# Aux_MCU_ATmega16U4.net
KiCad netlist of a schematic drawn in Altium Designer
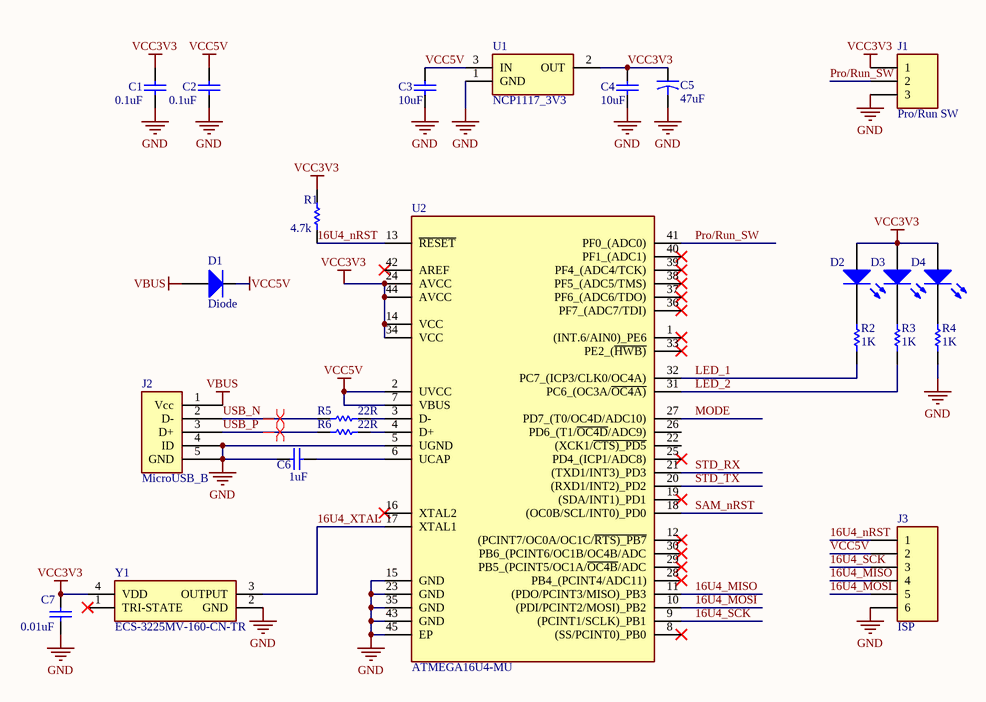
[diagram p0: Aux_MCU_ATmega16U4.SchDoc]

(export (version "E")
  (design (tool "Eeschema 10.0.6"))
  (components
    (comp (ref "C1")
      (value "0.1uF")
      (footprint "SMD0603")
      (description "Capacitor (Semiconductor SIM Model)")
      (fields (field (name "PUBLISHER") "Altium Limited"))
      (libsource (lib "Miscellaneous Devices") (part "Cap Semi"))
    )
    (comp (ref "C2")
      (value "0.1uF")
      (footprint "SMD0603")
      (description "Capacitor (Semiconductor SIM Model)")
      (fields (field (name "PUBLISHER") "Altium Limited"))
      (libsource (lib "Miscellaneous Devices") (part "Cap Semi"))
    )
    (comp (ref "C3")
      (value "10uF")
      (footprint "SMD0603")
      (description "Capacitor (Semiconductor SIM Model)")
      (fields (field (name "PUBLISHER") "Altium Limited"))
      (libsource (lib "Miscellaneous Devices") (part "Cap Semi"))
    )
    (comp (ref "C4")
      (value "10uF")
      (footprint "SMD0603")
      (description "Capacitor (Semiconductor SIM Model)")
      (fields (field (name "PUBLISHER") "Altium Limited"))
      (libsource (lib "Miscellaneous Devices") (part "Cap Semi"))
    )
    (comp (ref "C5")
      (value "47uF")
      (footprint "TAJ_CLASS_C")
      (description "Capacitor")
      (fields (field (name "PUBLISHER") "Altium Limited"))
      (libsource (lib "SRV8") (part "Cap2"))
    )
    (comp (ref "C6")
      (value "1uF")
      (footprint "SMD0603")
      (description "Capacitor (Semiconductor SIM Model)")
      (fields (field (name "PUBLISHER") "Altium Limited"))
      (libsource (lib "Miscellaneous Devices") (part "Cap Semi"))
    )
    (comp (ref "C7")
      (value "0.01uF")
      (footprint "SMD0603")
      (description "Capacitor (Semiconductor SIM Model)")
      (fields (field (name "PUBLISHER") "Altium Limited"))
      (libsource (lib "Miscellaneous Devices") (part "Cap Semi"))
    )
    (comp (ref "D1")
      (value "Diode")
      (footprint "SMB_DIODE_B130LB")
      (description "Default Diode")
      (fields (field (name "PUBLISHER") "Altium Limited"))
      (libsource (lib "Miscellaneous Devices") (part "Diode"))
    )
    (comp (ref "D2")
      (value "LED0")
      (footprint "SMD0603_LED")
      (description "Typical INFRARED GaAs LED")
      (fields (field (name "PUBLISHER") "Altium Limited"))
      (libsource (lib "Miscellaneous Devices") (part "LED0"))
    )
    (comp (ref "D3")
      (value "LED0")
      (footprint "SMD0603_LED")
      (description "Typical INFRARED GaAs LED")
      (fields (field (name "PUBLISHER") "Altium Limited"))
      (libsource (lib "Miscellaneous Devices") (part "LED0"))
    )
    (comp (ref "D4")
      (value "LED0")
      (footprint "SMD0603_LED")
      (description "Typical INFRARED GaAs LED")
      (fields (field (name "PUBLISHER") "Altium Limited"))
      (libsource (lib "Miscellaneous Devices") (part "LED0"))
    )
    (comp (ref "J1")
      (value "Pro/Run SW")
      (footprint "SLIDE_SW_3P")
      (description "Program/Run Switch")
      (libsource (lib "ATSAME54p20a_Ethernet") (part "Pro/Run SW"))
    )
    (comp (ref "J2")
      (value "MicroUSB_B")
      (footprint "micro_usb_molex_105017-0001")
      (libsource (lib "ATSAME54p20a_Ethernet") (part "MicroUSB_B"))
    )
    (comp (ref "J3") (value "ISP") (footprint "ISP") (libsource (lib "ATSAME54p20a_Ethernet") (part "ISP")))
    (comp (ref "R1")
      (value "4.7k")
      (footprint "SMD0603")
      (description "Semiconductor Resistor")
      (fields (field (name "Comment") "4.7K"))
      (libsource (lib "*") (part "Res"))
    )
    (comp (ref "R2")
      (value "1K")
      (footprint "SMD0603")
      (description "Semiconductor Resistor")
      (fields (field (name "PUBLISHER") "Altium Limited"))
      (libsource (lib "Miscellaneous Devices") (part "Res Semi"))
    )
    (comp (ref "R3")
      (value "1K")
      (footprint "SMD0603")
      (description "Semiconductor Resistor")
      (fields (field (name "PUBLISHER") "Altium Limited"))
      (libsource (lib "Miscellaneous Devices") (part "Res Semi"))
    )
    (comp (ref "R4")
      (value "1K")
      (footprint "SMD0603")
      (description "Semiconductor Resistor")
      (fields (field (name "PUBLISHER") "Altium Limited"))
      (libsource (lib "Miscellaneous Devices") (part "Res Semi"))
    )
    (comp (ref "R5")
      (value "22R")
      (footprint "SMD0603")
      (description "Semiconductor Resistor")
      (libsource (lib "*") (part "Res"))
    )
    (comp (ref "R6")
      (value "22R")
      (footprint "SMD0603")
      (description "Semiconductor Resistor")
      (libsource (lib "*") (part "Res"))
    )
    (comp (ref "U1")
      (value "NCP1117_3V3")
      (footprint "SOT-223-2")
      (description "IC REG 3.3V 1A DPAC")
      (libsource (lib "ATSAME54p20a_Ethernet") (part "NCP1117_3V3"))
    )
    (comp (ref "U2")
      (value "ATMEGA16U4-MU")
      (footprint "ATSAME54p20a_Ethernet:QFN50P700X700X100-45N-D")
      (description "Integrated Circuit")
      (libsource (lib "ATSAME54p20a_Ethernet") (part "ATMEGA16U4-MU"))
    )
    (comp (ref "Y1")
      (value "ECS-3225MV-160-CN-TR")
      (footprint "OSC3225")
      (description "Crystal or Oscillator")
      (fields (field (name "MOUSER2 PART NUMBER") "520-3225MV-160-CNT"))
      (libsource (lib "ATSAME54p20a_Ethernet") (part "ECS-3225MV-160-CN-TR"))
    )
  )
  (nets
    (net (code "1") (name "/16U4_MISO") (class "Default")
      (node (ref "J3") (pin "4") (pinfunction "4_4") (pintype "passive"))
      (node (ref "U2") (pin "11") (pinfunction "(PDO/PCINT3/MISO)_PB3_11") (pintype "passive"))
    )
    (net (code "2") (name "/16U4_MOSI") (class "Default")
      (node (ref "J3") (pin "5") (pinfunction "5_5") (pintype "passive"))
      (node (ref "U2") (pin "10") (pinfunction "(PDI/PCINT2/MOSI)_PB2_10") (pintype "passive"))
    )
    (net (code "3") (name "/16U4_SCK") (class "Default")
      (node (ref "J3") (pin "3") (pinfunction "3_3") (pintype "passive"))
      (node (ref "U2") (pin "9") (pinfunction "(PCINT1/SCLK)_PB1_9") (pintype "passive"))
    )
    (net (code "4") (name "/16U4_XTAL") (class "Default")
      (node (ref "U2") (pin "17") (pinfunction "XTAL1_17") (pintype "passive"))
      (node (ref "Y1") (pin "3") (pinfunction "OUTPUT_3") (pintype "passive"))
    )
    (net (code "5") (name "/16U4_nRST") (class "Default")
      (node (ref "J3") (pin "1") (pinfunction "1_1") (pintype "passive"))
      (node (ref "R1") (pin "1") (pinfunction "1_1") (pintype "passive"))
      (node (ref "U2") (pin "13") (pinfunction "~{RESET}_13") (pintype "passive"))
    )
    (net (code "6") (name "/LED_1") (class "Default")
      (node (ref "R2") (pin "1") (pinfunction "1_1") (pintype "passive"))
      (node (ref "U2") (pin "32") (pinfunction "PC7_(ICP3/CLK0/OC4A)_32") (pintype "passive"))
    )
    (net (code "7") (name "/LED_2") (class "Default")
      (node (ref "R3") (pin "1") (pinfunction "1_1") (pintype "passive"))
      (node (ref "U2") (pin "31") (pinfunction "PC6_(OC3A/~{OC4A)}_31") (pintype "passive"))
    )
    (net (code "8") (name "/MODE") (class "Default")
      (node (ref "U2") (pin "27") (pinfunction "PD7_(T0/OC4D/ADC10)_27") (pintype "passive"))
    )
    (net (code "9") (name "/Pro{slash}Run_SW") (class "Default")
      (node (ref "J1") (pin "2") (pinfunction "2_2") (pintype "passive"))
      (node (ref "U2") (pin "41") (pinfunction "PF0_(ADC0)_41") (pintype "passive"))
    )
    (net (code "10") (name "/SAM_nRST") (class "Default")
      (node (ref "U2") (pin "18") (pinfunction "(OC0B/SCL/INT0)_PD0_18") (pintype "passive"))
    )
    (net (code "11") (name "/STD_RX") (class "Default")
      (node (ref "U2") (pin "21") (pinfunction "(TXD1/INT3)_PD3_21") (pintype "passive"))
    )
    (net (code "12") (name "/STD_TX") (class "Default")
      (node (ref "U2") (pin "20") (pinfunction "(RXD1/INT2)_PD2_20") (pintype "passive"))
    )
    (net (code "13") (name "/USB_N") (class "Default")
      (node (ref "J2") (pin "2") (pinfunction "D-_2") (pintype "passive"))
      (node (ref "R5") (pin "2") (pinfunction "2_2") (pintype "passive"))
    )
    (net (code "14") (name "/USB_P") (class "Default")
      (node (ref "J2") (pin "3") (pinfunction "D+_3") (pintype "passive"))
      (node (ref "R6") (pin "2") (pinfunction "2_2") (pintype "passive"))
    )
    (net (code "15") (name "GND") (class "Default")
      (node (ref "C1") (pin "2") (pinfunction "2_2") (pintype "passive"))
      (node (ref "C2") (pin "2") (pinfunction "2_2") (pintype "passive"))
      (node (ref "C3") (pin "1") (pinfunction "1_1") (pintype "passive"))
      (node (ref "C4") (pin "1") (pinfunction "1_1") (pintype "passive"))
      (node (ref "C5") (pin "2") (pinfunction "2_2") (pintype "passive"))
      (node (ref "C6") (pin "1") (pinfunction "1_1") (pintype "passive"))
      (node (ref "C7") (pin "1") (pinfunction "1_1") (pintype "passive"))
      (node (ref "J1") (pin "3") (pinfunction "3_3") (pintype "passive"))
      (node (ref "J2") (pin "4") (pinfunction "ID_4") (pintype "passive"))
      (node (ref "J2") (pin "5") (pinfunction "GND_5") (pintype "passive"))
      (node (ref "J3") (pin "6") (pinfunction "6_6") (pintype "passive"))
      (node (ref "R4") (pin "1") (pinfunction "1_1") (pintype "passive"))
      (node (ref "U1") (pin "1") (pinfunction "GND_1") (pintype "passive"))
      (node (ref "U2") (pin "15") (pinfunction "GND_15") (pintype "passive"))
      (node (ref "U2") (pin "23") (pinfunction "GND_23") (pintype "passive"))
      (node (ref "U2") (pin "35") (pinfunction "GND_35") (pintype "passive"))
      (node (ref "U2") (pin "43") (pinfunction "GND_43") (pintype "passive"))
      (node (ref "U2") (pin "45") (pinfunction "EP_45") (pintype "passive"))
      (node (ref "U2") (pin "5") (pinfunction "UGND_5") (pintype "passive"))
      (node (ref "Y1") (pin "2") (pinfunction "GND_2") (pintype "passive"))
    )
    (net (code "16") (name "Net-(D2-K)") (class "Default")
      (node (ref "D2") (pin "2") (pinfunction "K_2") (pintype "passive"))
      (node (ref "R2") (pin "2") (pinfunction "2_2") (pintype "passive"))
    )
    (net (code "17") (name "Net-(D3-K)") (class "Default")
      (node (ref "D3") (pin "2") (pinfunction "K_2") (pintype "passive"))
      (node (ref "R3") (pin "2") (pinfunction "2_2") (pintype "passive"))
    )
    (net (code "18") (name "Net-(D4-K)") (class "Default")
      (node (ref "D4") (pin "2") (pinfunction "K_2") (pintype "passive"))
      (node (ref "R4") (pin "2") (pinfunction "2_2") (pintype "passive"))
    )
    (net (code "19") (name "Net-(U2-D+)") (class "Default")
      (node (ref "R6") (pin "1") (pinfunction "1_1") (pintype "passive"))
      (node (ref "U2") (pin "4") (pinfunction "D+_4") (pintype "passive"))
    )
    (net (code "20") (name "Net-(U2-D-)") (class "Default")
      (node (ref "R5") (pin "1") (pinfunction "1_1") (pintype "passive"))
      (node (ref "U2") (pin "3") (pinfunction "D-_3") (pintype "passive"))
    )
    (net (code "21") (name "Net-(U2-UCAP)") (class "Default")
      (node (ref "C6") (pin "2") (pinfunction "2_2") (pintype "passive"))
      (node (ref "U2") (pin "6") (pinfunction "UCAP_6") (pintype "passive"))
    )
    (net (code "22") (name "VBUS") (class "Default")
      (node (ref "D1") (pin "1") (pinfunction "A_1") (pintype "passive"))
      (node (ref "J2") (pin "1") (pinfunction "Vcc_1") (pintype "passive"))
    )
    (net (code "23") (name "VCC3V3") (class "Default")
      (node (ref "C1") (pin "1") (pinfunction "1_1") (pintype "passive"))
      (node (ref "C4") (pin "2") (pinfunction "2_2") (pintype "passive"))
      (node (ref "C5") (pin "1") (pinfunction "1_1") (pintype "passive"))
      (node (ref "C7") (pin "2") (pinfunction "2_2") (pintype "passive"))
      (node (ref "D2") (pin "1") (pinfunction "A_1") (pintype "passive"))
      (node (ref "D3") (pin "1") (pinfunction "A_1") (pintype "passive"))
      (node (ref "D4") (pin "1") (pinfunction "A_1") (pintype "passive"))
      (node (ref "J1") (pin "1") (pinfunction "1_1") (pintype "passive"))
      (node (ref "R1") (pin "2") (pinfunction "2_2") (pintype "passive"))
      (node (ref "U1") (pin "2") (pinfunction "OUT_2") (pintype "passive"))
      (node (ref "U2") (pin "14") (pinfunction "VCC_14") (pintype "passive"))
      (node (ref "U2") (pin "24") (pinfunction "AVCC_24") (pintype "passive"))
      (node (ref "U2") (pin "34") (pinfunction "VCC_34") (pintype "passive"))
      (node (ref "U2") (pin "44") (pinfunction "AVCC_44") (pintype "passive"))
      (node (ref "Y1") (pin "4") (pinfunction "VDD_4") (pintype "passive"))
    )
    (net (code "24") (name "VCC5V") (class "Default")
      (node (ref "C2") (pin "1") (pinfunction "1_1") (pintype "passive"))
      (node (ref "C3") (pin "2") (pinfunction "2_2") (pintype "passive"))
      (node (ref "D1") (pin "2") (pinfunction "K_2") (pintype "passive"))
      (node (ref "J3") (pin "2") (pinfunction "2_2") (pintype "passive"))
      (node (ref "U1") (pin "3") (pinfunction "IN_3") (pintype "passive"))
      (node (ref "U2") (pin "2") (pinfunction "UVCC_2") (pintype "passive"))
      (node (ref "U2") (pin "7") (pinfunction "VBUS_7") (pintype "passive"))
    )
    (net (code "25") (name "unconnected-(U2-(INT.6{slash}AIN0)_PE6-Pad1)") (class "Default")
      (node (ref "U2") (pin "1") (pinfunction "(INT.6/AIN0)_PE6_1") (pintype "passive+no_connect"))
    )
    (net (code "26") (name "unconnected-(U2-(PCINT7{slash}OC0A{slash}OC1C{slash}~{RTS)_PB7}-Pad12)") (class "Default")
      (node (ref "U2") (pin "12") (pinfunction "(PCINT7/OC0A/OC1C/~{RTS)_PB7}_12") (pintype "passive+no_connect"))
    )
    (net (code "27") (name "unconnected-(U2-(SDA{slash}INT1)_PD1-Pad19)") (class "Default")
      (node (ref "U2") (pin "19") (pinfunction "(SDA/INT1)_PD1_19") (pintype "passive+no_connect"))
    )
    (net (code "28") (name "unconnected-(U2-(SS{slash}PCINT0)_PB0-Pad8)") (class "Default")
      (node (ref "U2") (pin "8") (pinfunction "(SS/PCINT0)_PB0_8") (pintype "passive+no_connect"))
    )
    (net (code "29") (name "unconnected-(U2-(XCK1{slash}~{CTS)_PD5}-Pad22)") (class "Default")
      (node (ref "U2") (pin "22") (pinfunction "(XCK1/~{CTS)_PD5}_22") (pintype "passive"))
    )
    (net (code "30") (name "unconnected-(U2-AREF-Pad42)") (class "Default")
      (node (ref "U2") (pin "42") (pinfunction "AREF_42") (pintype "passive+no_connect"))
    )
    (net (code "31") (name "unconnected-(U2-PB4_(PCINT4{slash}ADC11)-Pad28)") (class "Default")
      (node (ref "U2") (pin "28") (pinfunction "PB4_(PCINT4/ADC11)_28") (pintype "passive+no_connect"))
    )
    (net (code "32") (name "unconnected-(U2-PB5_(PCINT5{slash}OC1A{slash}~{OC4B}{slash}ADC-Pad29)") (class "Default")
      (node (ref "U2") (pin "29") (pinfunction "PB5_(PCINT5/OC1A/~{OC4B}/ADC_29") (pintype "passive+no_connect"))
    )
    (net (code "33") (name "unconnected-(U2-PB6_(PCINT6{slash}OC1B{slash}OC4B{slash}ADC-Pad30)") (class "Default")
      (node (ref "U2") (pin "30") (pinfunction "PB6_(PCINT6/OC1B/OC4B/ADC_30") (pintype "passive+no_connect"))
    )
    (net (code "34") (name "unconnected-(U2-PD4_(ICP1{slash}ADC8)-Pad25)") (class "Default")
      (node (ref "U2") (pin "25") (pinfunction "PD4_(ICP1/ADC8)_25") (pintype "passive+no_connect"))
    )
    (net (code "35") (name "unconnected-(U2-PD6_(T1{slash}~{OC4D}{slash}ADC9)-Pad26)") (class "Default")
      (node (ref "U2") (pin "26") (pinfunction "PD6_(T1/~{OC4D}/ADC9)_26") (pintype "passive"))
    )
    (net (code "36") (name "unconnected-(U2-PE2_(~{HWB)}-Pad33)") (class "Default")
      (node (ref "U2") (pin "33") (pinfunction "PE2_(~{HWB)}_33") (pintype "passive+no_connect"))
    )
    (net (code "37") (name "unconnected-(U2-PF1_(ADC1)-Pad40)") (class "Default")
      (node (ref "U2") (pin "40") (pinfunction "PF1_(ADC1)_40") (pintype "passive+no_connect"))
    )
    (net (code "38") (name "unconnected-(U2-PF4_(ADC4{slash}TCK)-Pad39)") (class "Default")
      (node (ref "U2") (pin "39") (pinfunction "PF4_(ADC4/TCK)_39") (pintype "passive+no_connect"))
    )
    (net (code "39") (name "unconnected-(U2-PF5_(ADC5{slash}TMS)-Pad38)") (class "Default")
      (node (ref "U2") (pin "38") (pinfunction "PF5_(ADC5/TMS)_38") (pintype "passive+no_connect"))
    )
    (net (code "40") (name "unconnected-(U2-PF6_(ADC6{slash}TDO)-Pad37)") (class "Default")
      (node (ref "U2") (pin "37") (pinfunction "PF6_(ADC6/TDO)_37") (pintype "passive+no_connect"))
    )
    (net (code "41") (name "unconnected-(U2-PF7_(ADC7{slash}TDI)-Pad36)") (class "Default")
      (node (ref "U2") (pin "36") (pinfunction "PF7_(ADC7/TDI)_36") (pintype "passive+no_connect"))
    )
    (net (code "42") (name "unconnected-(U2-XTAL2-Pad16)") (class "Default")
      (node (ref "U2") (pin "16") (pinfunction "XTAL2_16") (pintype "passive+no_connect"))
    )
    (net (code "43") (name "unconnected-(Y1-TRI-STATE-Pad1)") (class "Default")
      (node (ref "Y1") (pin "1") (pinfunction "TRI-STATE_1") (pintype "passive+no_connect"))
    )
  )
)
